# ProPrj_mykeyboard_2025-10-05.net
KiCad netlist of a schematic drawn in EasyEDA Pro
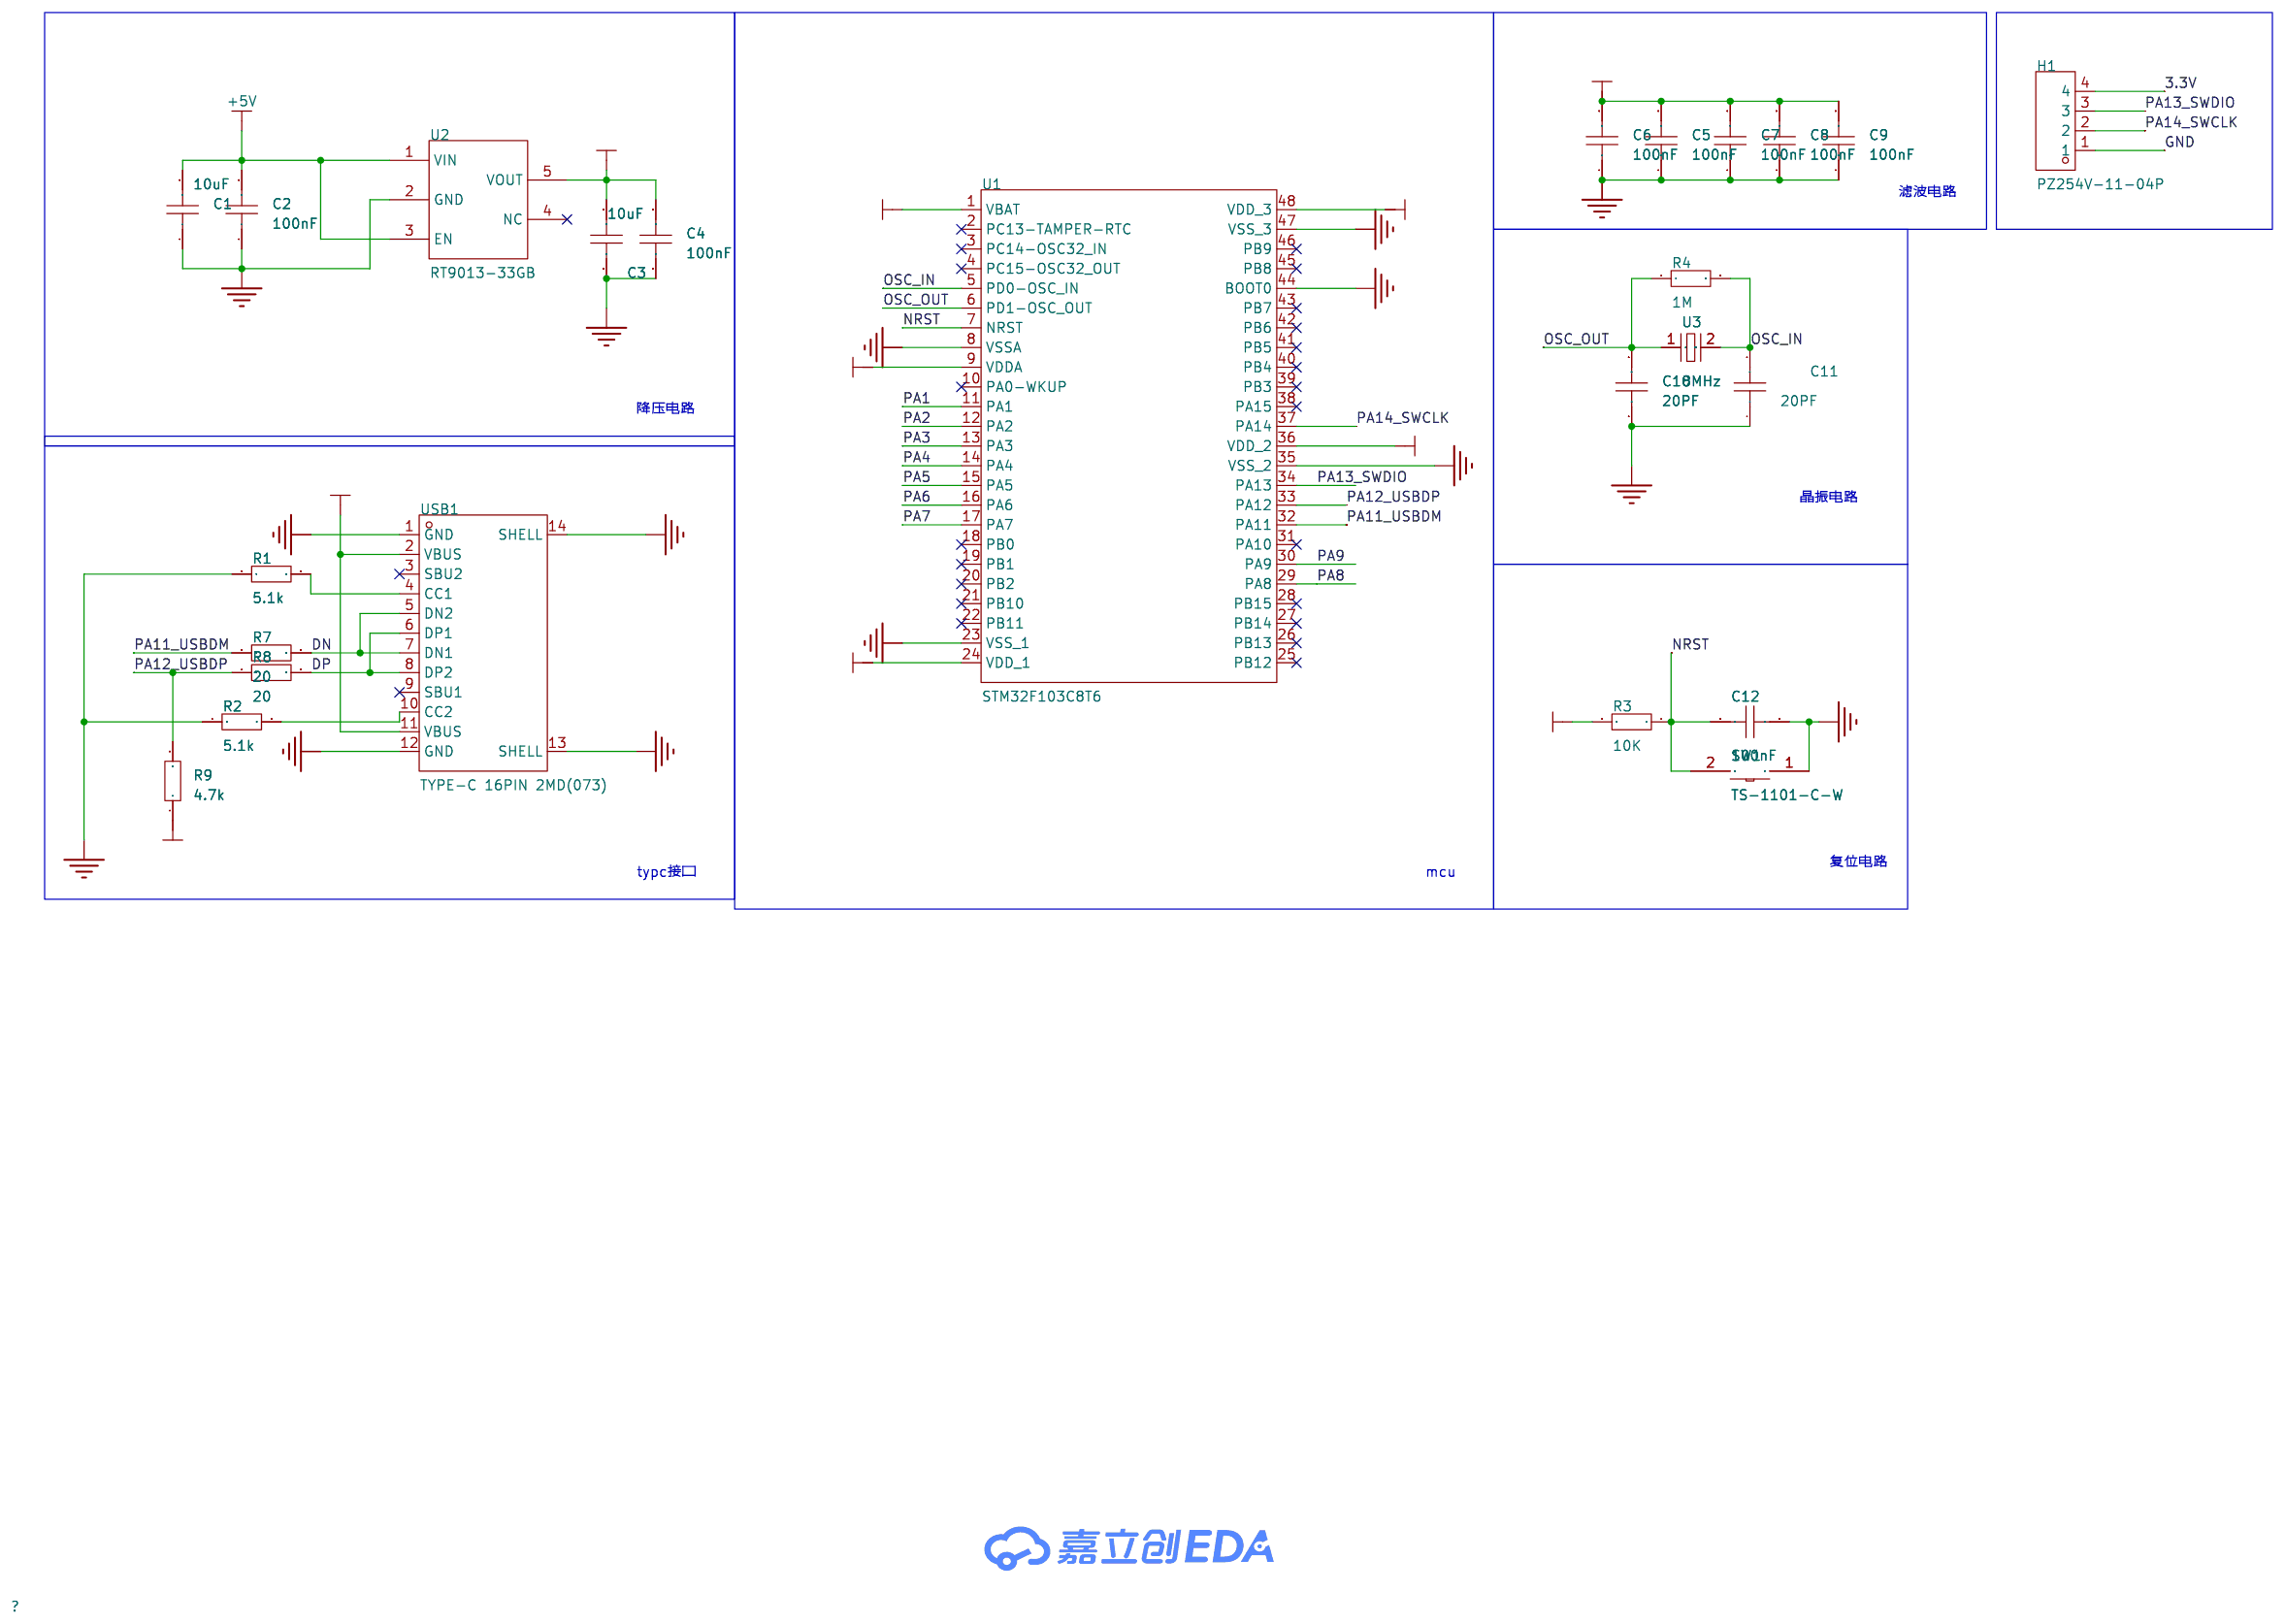
[diagram p0: P1]
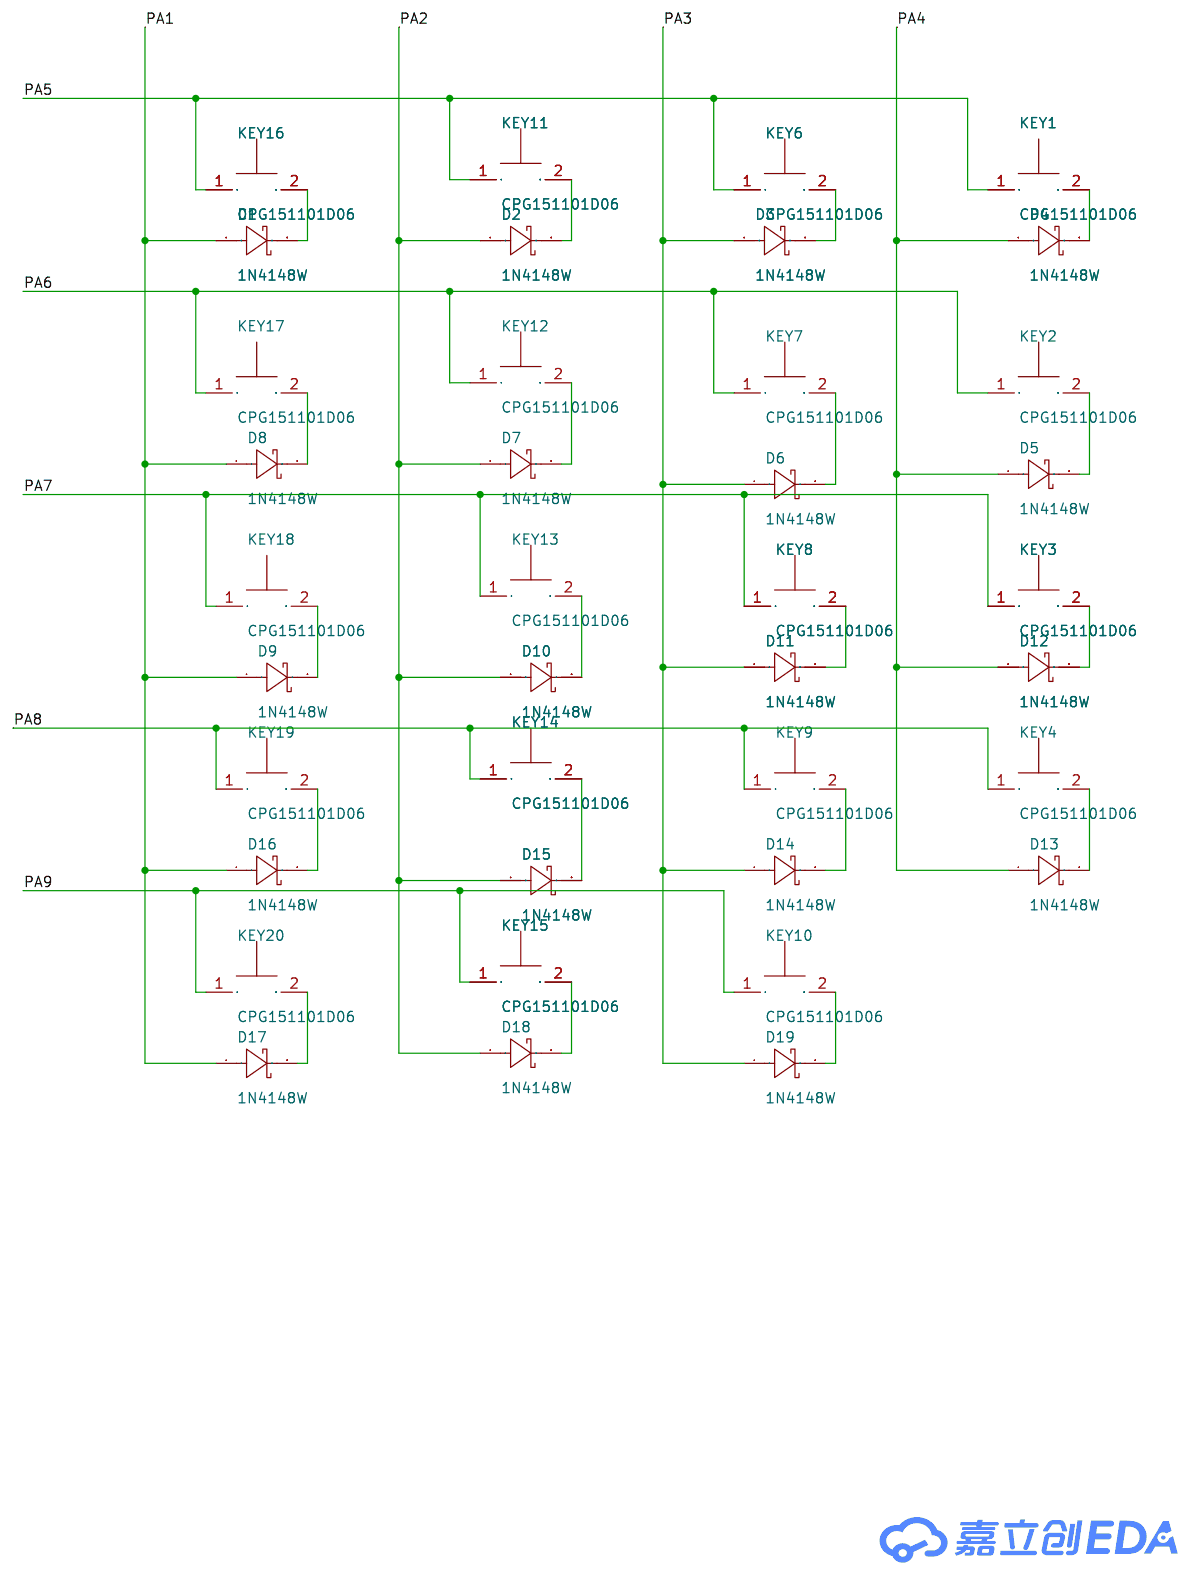
[diagram p1: P2]

(export (version "E")
  (design (tool "Eeschema 10.0.6"))
  (components
    (comp (ref "C1")
      (value "10uF")
      (footprint "easyedapro:C0603")
      (libsource (lib "easyedapro") (part "Capacitance"))
    )
    (comp (ref "C2")
      (value "100nF")
      (footprint "easyedapro:C0603")
      (libsource (lib "easyedapro") (part "Capacitance"))
    )
    (comp (ref "C3")
      (value "10uF")
      (footprint "easyedapro:C0603")
      (libsource (lib "easyedapro") (part "Capacitance"))
    )
    (comp (ref "C4")
      (value "100nF")
      (footprint "easyedapro:C0603")
      (libsource (lib "easyedapro") (part "Capacitance"))
    )
    (comp (ref "C5")
      (value "100nF")
      (footprint "easyedapro:C0603")
      (libsource (lib "easyedapro") (part "Capacitance"))
    )
    (comp (ref "C6")
      (value "100nF")
      (footprint "easyedapro:C0603")
      (libsource (lib "easyedapro") (part "Capacitance"))
    )
    (comp (ref "C7")
      (value "100nF")
      (footprint "easyedapro:C0603")
      (libsource (lib "easyedapro") (part "Capacitance"))
    )
    (comp (ref "C8")
      (value "100nF")
      (footprint "easyedapro:C0603")
      (libsource (lib "easyedapro") (part "Capacitance"))
    )
    (comp (ref "C9")
      (value "100nF")
      (footprint "easyedapro:C0603")
      (libsource (lib "easyedapro") (part "Capacitance"))
    )
    (comp (ref "C10")
      (value "20PF")
      (footprint "easyedapro:C0603")
      (libsource (lib "easyedapro") (part "Capacitance"))
    )
    (comp (ref "C11")
      (value "20PF")
      (footprint "easyedapro:C0603")
      (libsource (lib "easyedapro") (part "Capacitance"))
    )
    (comp (ref "C12")
      (value "100nF")
      (footprint "easyedapro:C0603")
      (libsource (lib "easyedapro") (part "Capacitance"))
    )
    (comp (ref "H1")
      (value "PZ254V-11-04P")
      (footprint "easyedapro:HDR-TH_4P-P2.54-V-M")
      (fields (field (name "Manufacturer") "XFCN(兴飞)"))
      (libsource (lib "easyedapro") (part "PZ254V-11-04P_C2691448"))
    )
    (comp (ref "R1") (value "5.1k") (footprint "easyedapro:R0603") (libsource (lib "easyedapro") (part "电阻")))
    (comp (ref "R2") (value "5.1k") (footprint "easyedapro:R0603") (libsource (lib "easyedapro") (part "电阻")))
    (comp (ref "R3") (value "10K") (footprint "easyedapro:R0603") (libsource (lib "easyedapro") (part "电阻")))
    (comp (ref "R4") (value "1M") (footprint "easyedapro:R0603") (libsource (lib "easyedapro") (part "电阻")))
    (comp (ref "R7") (value "20") (footprint "easyedapro:R0603") (libsource (lib "easyedapro") (part "电阻")))
    (comp (ref "R8") (value "20") (footprint "easyedapro:R0603") (libsource (lib "easyedapro") (part "电阻")))
    (comp (ref "R9") (value "4.7k") (footprint "easyedapro:R0603") (libsource (lib "easyedapro") (part "电阻")))
    (comp (ref "SW1")
      (value "TS-1101-C-W")
      (footprint "easyedapro:SW-SMD_L6.0-W3.3-LS8.0")
      (fields (field (name "Manufacturer") "XKB Connectivity(中国星坤)"))
      (libsource (lib "easyedapro") (part "TS-1101-C-W"))
    )
    (comp (ref "U1")
      (value "STM32F103C8T6")
      (footprint "easyedapro:LQFP-48_L7.0-W7.0-P0.50-LS9.0-BL")
      (description "CPU内核:ARM-M3;CPU最大主频:72MHz;应用领域:-;")
      (fields (field (name "Manufacturer") "ST(意法半导体)"))
      (libsource (lib "easyedapro") (part "STM32F103C8T6"))
    )
    (comp (ref "U2")
      (value "RT9013-33GB")
      (footprint "easyedapro:SOT-23-5_L3.0-W1.7-P0.95-LS2.8-BL")
      (description "输出类型:固定;工作电压:5.5V;输出电压:3.3V;输出电流:500mA;电源纹波抑制比(PSRR):50dB@(10kHz);输出极性:正极;")
      (fields (field (name "Manufacturer") "RICHTEK(立锜)"))
      (libsource (lib "easyedapro") (part "RT9013-33GB"))
    )
    (comp (ref "U3")
      (value "8MHz")
      (footprint "easyedapro:HC-49S_L7.0-W4.0")
      (description "频率:8MHz;常温频差:±20ppm;负载电容:20pF;频率稳定度:±30ppm;")
      (fields (field (name "Manufacturer Part") "8M 20PF 20PPM") (field (name "Manufacturer") "SOSET(索斯特)"))
      (libsource (lib "easyedapro") (part "8M 20PF 20PPM"))
    )
    (comp (ref "USB1")
      (value "TYPE-C 16PIN 2MD(073)")
      (footprint "easyedapro:USB-C-SMD_TYPE-C-6PIN-2MD-073")
      (description "连接器类型:Type-C;协议标准:-;公母:母;安装方式:卧贴;触点数量:16P;端口数量:1;额定电流 - 电源:3A;工作温度:-25°C~+85°C;")
      (fields (field (name "Manufacturer") "SHOU HAN(首韩)"))
      (libsource (lib "easyedapro") (part "TYPE-C 16PIN 2MD(073)"))
    )
    (comp (ref "D1")
      (value "1N4148W")
      (footprint "easyedapro:SOD-123_L2.7-W1.6-LS3.7-FD")
      (description "二极管配置:独立式;正向压降(Vf):1.25V@150mA;直流反向耐压(Vr):100V;整流电流:150mA;反向恢复时间(Trr):4ns;")
      (fields (field (name "Manufacturer") "R+O(宏嘉诚)"))
      (libsource (lib "easyedapro") (part "1N4148W_C7420318"))
    )
    (comp (ref "D2")
      (value "1N4148W")
      (footprint "easyedapro:SOD-123_L2.7-W1.6-LS3.7-FD")
      (description "二极管配置:独立式;正向压降(Vf):1.25V@150mA;直流反向耐压(Vr):100V;整流电流:150mA;反向恢复时间(Trr):4ns;")
      (fields (field (name "Manufacturer") "R+O(宏嘉诚)"))
      (libsource (lib "easyedapro") (part "1N4148W_C7420318"))
    )
    (comp (ref "D3")
      (value "1N4148W")
      (footprint "easyedapro:SOD-123_L2.7-W1.6-LS3.7-FD")
      (description "二极管配置:独立式;正向压降(Vf):1.25V@150mA;直流反向耐压(Vr):100V;整流电流:150mA;反向恢复时间(Trr):4ns;")
      (fields (field (name "Manufacturer") "R+O(宏嘉诚)"))
      (libsource (lib "easyedapro") (part "1N4148W_C7420318"))
    )
    (comp (ref "D4")
      (value "1N4148W")
      (footprint "easyedapro:SOD-123_L2.7-W1.6-LS3.7-FD")
      (description "二极管配置:独立式;正向压降(Vf):1.25V@150mA;直流反向耐压(Vr):100V;整流电流:150mA;反向恢复时间(Trr):4ns;")
      (fields (field (name "Manufacturer") "R+O(宏嘉诚)"))
      (libsource (lib "easyedapro") (part "1N4148W_C7420318"))
    )
    (comp (ref "D5")
      (value "1N4148W")
      (footprint "easyedapro:SOD-123_L2.7-W1.6-LS3.7-FD")
      (description "二极管配置:独立式;正向压降(Vf):1.25V@150mA;直流反向耐压(Vr):100V;整流电流:150mA;反向恢复时间(Trr):4ns;")
      (fields (field (name "Manufacturer") "R+O(宏嘉诚)"))
      (libsource (lib "easyedapro") (part "1N4148W_C7420318"))
    )
    (comp (ref "D6")
      (value "1N4148W")
      (footprint "easyedapro:SOD-123_L2.7-W1.6-LS3.7-FD")
      (description "二极管配置:独立式;正向压降(Vf):1.25V@150mA;直流反向耐压(Vr):100V;整流电流:150mA;反向恢复时间(Trr):4ns;")
      (fields (field (name "Manufacturer") "R+O(宏嘉诚)"))
      (libsource (lib "easyedapro") (part "1N4148W_C7420318"))
    )
    (comp (ref "D7")
      (value "1N4148W")
      (footprint "easyedapro:SOD-123_L2.7-W1.6-LS3.7-FD")
      (description "二极管配置:独立式;正向压降(Vf):1.25V@150mA;直流反向耐压(Vr):100V;整流电流:150mA;反向恢复时间(Trr):4ns;")
      (fields (field (name "Manufacturer") "R+O(宏嘉诚)"))
      (libsource (lib "easyedapro") (part "1N4148W_C7420318"))
    )
    (comp (ref "D8")
      (value "1N4148W")
      (footprint "easyedapro:SOD-123_L2.7-W1.6-LS3.7-FD")
      (description "二极管配置:独立式;正向压降(Vf):1.25V@150mA;直流反向耐压(Vr):100V;整流电流:150mA;反向恢复时间(Trr):4ns;")
      (fields (field (name "Manufacturer") "R+O(宏嘉诚)"))
      (libsource (lib "easyedapro") (part "1N4148W_C7420318"))
    )
    (comp (ref "D9")
      (value "1N4148W")
      (footprint "easyedapro:SOD-123_L2.7-W1.6-LS3.7-FD")
      (description "二极管配置:独立式;正向压降(Vf):1.25V@150mA;直流反向耐压(Vr):100V;整流电流:150mA;反向恢复时间(Trr):4ns;")
      (fields (field (name "Manufacturer") "R+O(宏嘉诚)"))
      (libsource (lib "easyedapro") (part "1N4148W_C7420318"))
    )
    (comp (ref "D10")
      (value "1N4148W")
      (footprint "easyedapro:SOD-123_L2.7-W1.6-LS3.7-FD")
      (description "二极管配置:独立式;正向压降(Vf):1.25V@150mA;直流反向耐压(Vr):100V;整流电流:150mA;反向恢复时间(Trr):4ns;")
      (fields (field (name "Manufacturer") "R+O(宏嘉诚)"))
      (libsource (lib "easyedapro") (part "1N4148W_C7420318"))
    )
    (comp (ref "D11")
      (value "1N4148W")
      (footprint "easyedapro:SOD-123_L2.7-W1.6-LS3.7-FD")
      (description "二极管配置:独立式;正向压降(Vf):1.25V@150mA;直流反向耐压(Vr):100V;整流电流:150mA;反向恢复时间(Trr):4ns;")
      (fields (field (name "Manufacturer") "R+O(宏嘉诚)"))
      (libsource (lib "easyedapro") (part "1N4148W_C7420318"))
    )
    (comp (ref "D12")
      (value "1N4148W")
      (footprint "easyedapro:SOD-123_L2.7-W1.6-LS3.7-FD")
      (description "二极管配置:独立式;正向压降(Vf):1.25V@150mA;直流反向耐压(Vr):100V;整流电流:150mA;反向恢复时间(Trr):4ns;")
      (fields (field (name "Manufacturer") "R+O(宏嘉诚)"))
      (libsource (lib "easyedapro") (part "1N4148W_C7420318"))
    )
    (comp (ref "D13")
      (value "1N4148W")
      (footprint "easyedapro:SOD-123_L2.7-W1.6-LS3.7-FD")
      (description "二极管配置:独立式;正向压降(Vf):1.25V@150mA;直流反向耐压(Vr):100V;整流电流:150mA;反向恢复时间(Trr):4ns;")
      (fields (field (name "Manufacturer") "R+O(宏嘉诚)"))
      (libsource (lib "easyedapro") (part "1N4148W_C7420318"))
    )
    (comp (ref "D14")
      (value "1N4148W")
      (footprint "easyedapro:SOD-123_L2.7-W1.6-LS3.7-FD")
      (description "二极管配置:独立式;正向压降(Vf):1.25V@150mA;直流反向耐压(Vr):100V;整流电流:150mA;反向恢复时间(Trr):4ns;")
      (fields (field (name "Manufacturer") "R+O(宏嘉诚)"))
      (libsource (lib "easyedapro") (part "1N4148W_C7420318"))
    )
    (comp (ref "D15")
      (value "1N4148W")
      (footprint "easyedapro:SOD-123_L2.7-W1.6-LS3.7-FD")
      (description "二极管配置:独立式;正向压降(Vf):1.25V@150mA;直流反向耐压(Vr):100V;整流电流:150mA;反向恢复时间(Trr):4ns;")
      (fields (field (name "Manufacturer") "R+O(宏嘉诚)"))
      (libsource (lib "easyedapro") (part "1N4148W_C7420318"))
    )
    (comp (ref "D16")
      (value "1N4148W")
      (footprint "easyedapro:SOD-123_L2.7-W1.6-LS3.7-FD")
      (description "二极管配置:独立式;正向压降(Vf):1.25V@150mA;直流反向耐压(Vr):100V;整流电流:150mA;反向恢复时间(Trr):4ns;")
      (fields (field (name "Manufacturer") "R+O(宏嘉诚)"))
      (libsource (lib "easyedapro") (part "1N4148W_C7420318"))
    )
    (comp (ref "D17")
      (value "1N4148W")
      (footprint "easyedapro:SOD-123_L2.7-W1.6-LS3.7-FD")
      (description "二极管配置:独立式;正向压降(Vf):1.25V@150mA;直流反向耐压(Vr):100V;整流电流:150mA;反向恢复时间(Trr):4ns;")
      (fields (field (name "Manufacturer") "R+O(宏嘉诚)"))
      (libsource (lib "easyedapro") (part "1N4148W_C7420318"))
    )
    (comp (ref "D18")
      (value "1N4148W")
      (footprint "easyedapro:SOD-123_L2.7-W1.6-LS3.7-FD")
      (description "二极管配置:独立式;正向压降(Vf):1.25V@150mA;直流反向耐压(Vr):100V;整流电流:150mA;反向恢复时间(Trr):4ns;")
      (fields (field (name "Manufacturer") "R+O(宏嘉诚)"))
      (libsource (lib "easyedapro") (part "1N4148W_C7420318"))
    )
    (comp (ref "D19")
      (value "1N4148W")
      (footprint "easyedapro:SOD-123_L2.7-W1.6-LS3.7-FD")
      (description "二极管配置:独立式;正向压降(Vf):1.25V@150mA;直流反向耐压(Vr):100V;整流电流:150mA;反向恢复时间(Trr):4ns;")
      (fields (field (name "Manufacturer") "R+O(宏嘉诚)"))
      (libsource (lib "easyedapro") (part "1N4148W_C7420318"))
    )
    (comp (ref "KEY1")
      (value "CPG151101D06")
      (footprint "easyedapro:KEY-TH_CPG151101D06")
      (description "机械键盘开关MX茶轴 段落手感")
      (fields (field (name "Manufacturer") "HanElectricity(瀚源)"))
      (libsource (lib "easyedapro") (part "CPG151101D06"))
    )
    (comp (ref "KEY2")
      (value "CPG151101D06")
      (footprint "easyedapro:KEY-TH_CPG151101D06")
      (description "机械键盘开关MX茶轴 段落手感")
      (fields (field (name "Manufacturer") "HanElectricity(瀚源)"))
      (libsource (lib "easyedapro") (part "CPG151101D06"))
    )
    (comp (ref "KEY3")
      (value "CPG151101D06")
      (footprint "easyedapro:KEY-TH_CPG151101D06")
      (description "机械键盘开关MX茶轴 段落手感")
      (fields (field (name "Manufacturer") "HanElectricity(瀚源)"))
      (libsource (lib "easyedapro") (part "CPG151101D06"))
    )
    (comp (ref "KEY4")
      (value "CPG151101D06")
      (footprint "easyedapro:KEY-TH_CPG151101D06")
      (description "机械键盘开关MX茶轴 段落手感")
      (fields (field (name "Manufacturer") "HanElectricity(瀚源)"))
      (libsource (lib "easyedapro") (part "CPG151101D06"))
    )
    (comp (ref "KEY6")
      (value "CPG151101D06")
      (footprint "easyedapro:KEY-TH_CPG151101D06")
      (description "机械键盘开关MX茶轴 段落手感")
      (fields (field (name "Manufacturer") "HanElectricity(瀚源)"))
      (libsource (lib "easyedapro") (part "CPG151101D06"))
    )
    (comp (ref "KEY7")
      (value "CPG151101D06")
      (footprint "easyedapro:KEY-TH_CPG151101D06")
      (description "机械键盘开关MX茶轴 段落手感")
      (fields (field (name "Manufacturer") "HanElectricity(瀚源)"))
      (libsource (lib "easyedapro") (part "CPG151101D06"))
    )
    (comp (ref "KEY8")
      (value "CPG151101D06")
      (footprint "easyedapro:KEY-TH_CPG151101D06")
      (description "机械键盘开关MX茶轴 段落手感")
      (fields (field (name "Manufacturer") "HanElectricity(瀚源)"))
      (libsource (lib "easyedapro") (part "CPG151101D06"))
    )
    (comp (ref "KEY9")
      (value "CPG151101D06")
      (footprint "easyedapro:KEY-TH_CPG151101D06")
      (description "机械键盘开关MX茶轴 段落手感")
      (fields (field (name "Manufacturer") "HanElectricity(瀚源)"))
      (libsource (lib "easyedapro") (part "CPG151101D06"))
    )
    (comp (ref "KEY10")
      (value "CPG151101D06")
      (footprint "easyedapro:KEY-TH_CPG151101D06")
      (description "机械键盘开关MX茶轴 段落手感")
      (fields (field (name "Manufacturer") "HanElectricity(瀚源)"))
      (libsource (lib "easyedapro") (part "CPG151101D06"))
    )
    (comp (ref "KEY11")
      (value "CPG151101D06")
      (footprint "easyedapro:KEY-TH_CPG151101D06")
      (description "机械键盘开关MX茶轴 段落手感")
      (fields (field (name "Manufacturer") "HanElectricity(瀚源)"))
      (libsource (lib "easyedapro") (part "CPG151101D06"))
    )
    (comp (ref "KEY12")
      (value "CPG151101D06")
      (footprint "easyedapro:KEY-TH_CPG151101D06")
      (description "机械键盘开关MX茶轴 段落手感")
      (fields (field (name "Manufacturer") "HanElectricity(瀚源)"))
      (libsource (lib "easyedapro") (part "CPG151101D06"))
    )
    (comp (ref "KEY13")
      (value "CPG151101D06")
      (footprint "easyedapro:KEY-TH_CPG151101D06")
      (description "机械键盘开关MX茶轴 段落手感")
      (fields (field (name "Manufacturer") "HanElectricity(瀚源)"))
      (libsource (lib "easyedapro") (part "CPG151101D06"))
    )
    (comp (ref "KEY14")
      (value "CPG151101D06")
      (footprint "easyedapro:KEY-TH_CPG151101D06")
      (description "机械键盘开关MX茶轴 段落手感")
      (fields (field (name "Manufacturer") "HanElectricity(瀚源)"))
      (libsource (lib "easyedapro") (part "CPG151101D06"))
    )
    (comp (ref "KEY15")
      (value "CPG151101D06")
      (footprint "easyedapro:KEY-TH_CPG151101D06")
      (description "机械键盘开关MX茶轴 段落手感")
      (fields (field (name "Manufacturer") "HanElectricity(瀚源)"))
      (libsource (lib "easyedapro") (part "CPG151101D06"))
    )
    (comp (ref "KEY16")
      (value "CPG151101D06")
      (footprint "easyedapro:KEY-TH_CPG151101D06")
      (description "机械键盘开关MX茶轴 段落手感")
      (fields (field (name "Manufacturer") "HanElectricity(瀚源)"))
      (libsource (lib "easyedapro") (part "CPG151101D06"))
    )
    (comp (ref "KEY17")
      (value "CPG151101D06")
      (footprint "easyedapro:KEY-TH_CPG151101D06")
      (description "机械键盘开关MX茶轴 段落手感")
      (fields (field (name "Manufacturer") "HanElectricity(瀚源)"))
      (libsource (lib "easyedapro") (part "CPG151101D06"))
    )
    (comp (ref "KEY18")
      (value "CPG151101D06")
      (footprint "easyedapro:KEY-TH_CPG151101D06")
      (description "机械键盘开关MX茶轴 段落手感")
      (fields (field (name "Manufacturer") "HanElectricity(瀚源)"))
      (libsource (lib "easyedapro") (part "CPG151101D06"))
    )
    (comp (ref "KEY19")
      (value "CPG151101D06")
      (footprint "easyedapro:KEY-TH_CPG151101D06")
      (description "机械键盘开关MX茶轴 段落手感")
      (fields (field (name "Manufacturer") "HanElectricity(瀚源)"))
      (libsource (lib "easyedapro") (part "CPG151101D06"))
    )
    (comp (ref "KEY20")
      (value "CPG151101D06")
      (footprint "easyedapro:KEY-TH_CPG151101D06")
      (description "机械键盘开关MX茶轴 段落手感")
      (fields (field (name "Manufacturer") "HanElectricity(瀚源)"))
      (libsource (lib "easyedapro") (part "CPG151101D06"))
    )
  )
  (nets
    (net (code "1") (name "+5V") (class "Default")
      (node (ref "C1") (pin "2") (pinfunction "2_2") (pintype "input"))
      (node (ref "C2") (pin "2") (pinfunction "2_2") (pintype "input"))
      (node (ref "U2") (pin "1") (pinfunction "VIN_1") (pintype "unspecified"))
      (node (ref "U2") (pin "3") (pinfunction "EN_3") (pintype "unspecified"))
      (node (ref "USB1") (pin "11") (pinfunction "VBUS_11") (pintype "unspecified"))
      (node (ref "USB1") (pin "2") (pinfunction "VBUS_2") (pintype "unspecified"))
    )
    (net (code "2") (name "3.3V") (class "Default")
      (node (ref "C3") (pin "2") (pinfunction "2_2") (pintype "input"))
      (node (ref "C4") (pin "2") (pinfunction "2_2") (pintype "input"))
      (node (ref "C5") (pin "2") (pinfunction "2_2") (pintype "input"))
      (node (ref "C6") (pin "2") (pinfunction "2_2") (pintype "input"))
      (node (ref "C7") (pin "2") (pinfunction "2_2") (pintype "input"))
      (node (ref "C8") (pin "2") (pinfunction "2_2") (pintype "input"))
      (node (ref "C9") (pin "2") (pinfunction "2_2") (pintype "input"))
      (node (ref "H1") (pin "4") (pinfunction "4_4") (pintype "unspecified"))
      (node (ref "R3") (pin "2") (pinfunction "2_2") (pintype "input"))
      (node (ref "R9") (pin "1") (pinfunction "1_1") (pintype "input"))
      (node (ref "U1") (pin "1") (pinfunction "VBAT_1") (pintype "unspecified"))
      (node (ref "U1") (pin "24") (pinfunction "VDD_1_24") (pintype "unspecified"))
      (node (ref "U1") (pin "36") (pinfunction "VDD_2_36") (pintype "unspecified"))
      (node (ref "U1") (pin "48") (pinfunction "VDD_3_48") (pintype "unspecified"))
      (node (ref "U1") (pin "9") (pinfunction "VDDA_9") (pintype "unspecified"))
      (node (ref "U2") (pin "5") (pinfunction "VOUT_5") (pintype "unspecified"))
    )
    (net (code "3") (name "DN") (class "Default")
      (node (ref "R7") (pin "2") (pinfunction "2_2") (pintype "input"))
      (node (ref "USB1") (pin "5") (pinfunction "DN2_5") (pintype "unspecified"))
      (node (ref "USB1") (pin "7") (pinfunction "DN1_7") (pintype "unspecified"))
    )
    (net (code "4") (name "DP") (class "Default")
      (node (ref "R8") (pin "2") (pinfunction "2_2") (pintype "input"))
      (node (ref "USB1") (pin "6") (pinfunction "DP1_6") (pintype "unspecified"))
      (node (ref "USB1") (pin "8") (pinfunction "DP2_8") (pintype "unspecified"))
    )
    (net (code "5") (name "GND") (class "Default")
      (node (ref "C1") (pin "1") (pinfunction "1_1") (pintype "input"))
      (node (ref "C10") (pin "1") (pinfunction "1_1") (pintype "input"))
      (node (ref "C11") (pin "1") (pinfunction "1_1") (pintype "input"))
      (node (ref "C12") (pin "1") (pinfunction "1_1") (pintype "input"))
      (node (ref "C2") (pin "1") (pinfunction "1_1") (pintype "input"))
      (node (ref "C3") (pin "1") (pinfunction "1_1") (pintype "input"))
      (node (ref "C4") (pin "1") (pinfunction "1_1") (pintype "input"))
      (node (ref "C5") (pin "1") (pinfunction "1_1") (pintype "input"))
      (node (ref "C6") (pin "1") (pinfunction "1_1") (pintype "input"))
      (node (ref "C7") (pin "1") (pinfunction "1_1") (pintype "input"))
      (node (ref "C8") (pin "1") (pinfunction "1_1") (pintype "input"))
      (node (ref "C9") (pin "1") (pinfunction "1_1") (pintype "input"))
      (node (ref "H1") (pin "1") (pinfunction "1_1") (pintype "unspecified"))
      (node (ref "R1") (pin "1") (pinfunction "1_1") (pintype "input"))
      (node (ref "R2") (pin "1") (pinfunction "1_1") (pintype "input"))
      (node (ref "SW1") (pin "1") (pinfunction "1_1") (pintype "unspecified"))
      (node (ref "U1") (pin "23") (pinfunction "VSS_1_23") (pintype "unspecified"))
      (node (ref "U1") (pin "35") (pinfunction "VSS_2_35") (pintype "unspecified"))
      (node (ref "U1") (pin "44") (pinfunction "BOOT0_44") (pintype "unspecified"))
      (node (ref "U1") (pin "47") (pinfunction "VSS_3_47") (pintype "unspecified"))
      (node (ref "U1") (pin "8") (pinfunction "VSSA_8") (pintype "unspecified"))
      (node (ref "U2") (pin "2") (pinfunction "GND_2") (pintype "unspecified"))
      (node (ref "USB1") (pin "1") (pinfunction "GND_1") (pintype "unspecified"))
      (node (ref "USB1") (pin "12") (pinfunction "GND_12") (pintype "unspecified"))
      (node (ref "USB1") (pin "13") (pinfunction "SHELL_13") (pintype "unspecified"))
      (node (ref "USB1") (pin "14") (pinfunction "SHELL_14") (pintype "unspecified"))
    )
    (net (code "6") (name "NRST") (class "Default")
      (node (ref "C12") (pin "2") (pinfunction "2_2") (pintype "input"))
      (node (ref "R3") (pin "1") (pinfunction "1_1") (pintype "input"))
      (node (ref "SW1") (pin "2") (pinfunction "2_2") (pintype "unspecified"))
      (node (ref "U1") (pin "7") (pinfunction "NRST_7") (pintype "unspecified"))
    )
    (net (code "7") (name "Net-(D1-K)") (class "Default")
      (node (ref "D1") (pin "2") (pinfunction "K_2") (pintype "unspecified"))
      (node (ref "KEY16") (pin "2") (pinfunction "2_2") (pintype "unspecified"))
    )
    (net (code "8") (name "Net-(D2-K)") (class "Default")
      (node (ref "D2") (pin "2") (pinfunction "K_2") (pintype "unspecified"))
      (node (ref "KEY11") (pin "2") (pinfunction "2_2") (pintype "unspecified"))
    )
    (net (code "9") (name "Net-(D3-K)") (class "Default")
      (node (ref "D3") (pin "2") (pinfunction "K_2") (pintype "unspecified"))
      (node (ref "KEY6") (pin "2") (pinfunction "2_2") (pintype "unspecified"))
    )
    (net (code "10") (name "Net-(D4-K)") (class "Default")
      (node (ref "D4") (pin "2") (pinfunction "K_2") (pintype "unspecified"))
      (node (ref "KEY1") (pin "2") (pinfunction "2_2") (pintype "unspecified"))
    )
    (net (code "11") (name "Net-(D5-K)") (class "Default")
      (node (ref "D5") (pin "2") (pinfunction "K_2") (pintype "unspecified"))
      (node (ref "KEY2") (pin "2") (pinfunction "2_2") (pintype "unspecified"))
    )
    (net (code "12") (name "Net-(D6-K)") (class "Default")
      (node (ref "D6") (pin "2") (pinfunction "K_2") (pintype "unspecified"))
      (node (ref "KEY7") (pin "2") (pinfunction "2_2") (pintype "unspecified"))
    )
    (net (code "13") (name "Net-(D7-K)") (class "Default")
      (node (ref "D7") (pin "2") (pinfunction "K_2") (pintype "unspecified"))
      (node (ref "KEY12") (pin "2") (pinfunction "2_2") (pintype "unspecified"))
    )
    (net (code "14") (name "Net-(D8-K)") (class "Default")
      (node (ref "D8") (pin "2") (pinfunction "K_2") (pintype "unspecified"))
      (node (ref "KEY17") (pin "2") (pinfunction "2_2") (pintype "unspecified"))
    )
    (net (code "15") (name "Net-(D9-K)") (class "Default")
      (node (ref "D9") (pin "2") (pinfunction "K_2") (pintype "unspecified"))
      (node (ref "KEY18") (pin "2") (pinfunction "2_2") (pintype "unspecified"))
    )
    (net (code "16") (name "Net-(D10-K)") (class "Default")
      (node (ref "D10") (pin "2") (pinfunction "K_2") (pintype "unspecified"))
      (node (ref "KEY13") (pin "2") (pinfunction "2_2") (pintype "unspecified"))
    )
    (net (code "17") (name "Net-(D11-K)") (class "Default")
      (node (ref "D11") (pin "2") (pinfunction "K_2") (pintype "unspecified"))
      (node (ref "KEY8") (pin "2") (pinfunction "2_2") (pintype "unspecified"))
    )
    (net (code "18") (name "Net-(D12-K)") (class "Default")
      (node (ref "D12") (pin "2") (pinfunction "K_2") (pintype "unspecified"))
      (node (ref "KEY3") (pin "2") (pinfunction "2_2") (pintype "unspecified"))
    )
    (net (code "19") (name "Net-(D13-K)") (class "Default")
      (node (ref "D13") (pin "2") (pinfunction "K_2") (pintype "unspecified"))
      (node (ref "KEY4") (pin "2") (pinfunction "2_2") (pintype "unspecified"))
    )
    (net (code "20") (name "Net-(D14-K)") (class "Default")
      (node (ref "D14") (pin "2") (pinfunction "K_2") (pintype "unspecified"))
      (node (ref "KEY9") (pin "2") (pinfunction "2_2") (pintype "unspecified"))
    )
    (net (code "21") (name "Net-(D15-K)") (class "Default")
      (node (ref "D15") (pin "2") (pinfunction "K_2") (pintype "unspecified"))
      (node (ref "KEY14") (pin "2") (pinfunction "2_2") (pintype "unspecified"))
    )
    (net (code "22") (name "Net-(D16-K)") (class "Default")
      (node (ref "D16") (pin "2") (pinfunction "K_2") (pintype "unspecified"))
      (node (ref "KEY19") (pin "2") (pinfunction "2_2") (pintype "unspecified"))
    )
    (net (code "23") (name "Net-(D17-K)") (class "Default")
      (node (ref "D17") (pin "2") (pinfunction "K_2") (pintype "unspecified"))
      (node (ref "KEY20") (pin "2") (pinfunction "2_2") (pintype "unspecified"))
    )
    (net (code "24") (name "Net-(D18-K)") (class "Default")
      (node (ref "D18") (pin "2") (pinfunction "K_2") (pintype "unspecified"))
      (node (ref "KEY15") (pin "2") (pinfunction "2_2") (pintype "unspecified"))
    )
    (net (code "25") (name "Net-(D19-K)") (class "Default")
      (node (ref "D19") (pin "2") (pinfunction "K_2") (pintype "unspecified"))
      (node (ref "KEY10") (pin "2") (pinfunction "2_2") (pintype "unspecified"))
    )
    (net (code "26") (name "Net-(USB1-CC1)") (class "Default")
      (node (ref "R1") (pin "2") (pinfunction "2_2") (pintype "input"))
      (node (ref "USB1") (pin "4") (pinfunction "CC1_4") (pintype "unspecified"))
    )
    (net (code "27") (name "Net-(USB1-CC2)") (class "Default")
      (node (ref "R2") (pin "2") (pinfunction "2_2") (pintype "input"))
      (node (ref "USB1") (pin "10") (pinfunction "CC2_10") (pintype "unspecified"))
    )
    (net (code "28") (name "OSC_IN") (class "Default")
      (node (ref "C11") (pin "2") (pinfunction "2_2") (pintype "input"))
      (node (ref "R4") (pin "2") (pinfunction "2_2") (pintype "input"))
      (node (ref "U1") (pin "5") (pinfunction "PD0-OSC_IN_5") (pintype "unspecified"))
      (node (ref "U3") (pin "2") (pinfunction "GND_2") (pintype "input"))
    )
    (net (code "29") (name "OSC_OUT") (class "Default")
      (node (ref "C10") (pin "2") (pinfunction "2_2") (pintype "input"))
      (node (ref "R4") (pin "1") (pinfunction "1_1") (pintype "input"))
      (node (ref "U1") (pin "6") (pinfunction "PD1-OSC_OUT_6") (pintype "unspecified"))
      (node (ref "U3") (pin "1") (pinfunction "1_1") (pintype "input"))
    )
    (net (code "30") (name "PA1") (class "Default")
      (node (ref "D1") (pin "1") (pinfunction "A_1") (pintype "unspecified"))
      (node (ref "D16") (pin "1") (pinfunction "A_1") (pintype "unspecified"))
      (node (ref "D17") (pin "1") (pinfunction "A_1") (pintype "unspecified"))
      (node (ref "D8") (pin "1") (pinfunction "A_1") (pintype "unspecified"))
      (node (ref "D9") (pin "1") (pinfunction "A_1") (pintype "unspecified"))
      (node (ref "U1") (pin "11") (pinfunction "PA1_11") (pintype "unspecified"))
    )
    (net (code "31") (name "PA2") (class "Default")
      (node (ref "D10") (pin "1") (pinfunction "A_1") (pintype "unspecified"))
      (node (ref "D15") (pin "1") (pinfunction "A_1") (pintype "unspecified"))
      (node (ref "D18") (pin "1") (pinfunction "A_1") (pintype "unspecified"))
      (node (ref "D2") (pin "1") (pinfunction "A_1") (pintype "unspecified"))
      (node (ref "D7") (pin "1") (pinfunction "A_1") (pintype "unspecified"))
      (node (ref "U1") (pin "12") (pinfunction "PA2_12") (pintype "unspecified"))
    )
    (net (code "32") (name "PA3") (class "Default")
      (node (ref "D11") (pin "1") (pinfunction "A_1") (pintype "unspecified"))
      (node (ref "D14") (pin "1") (pinfunction "A_1") (pintype "unspecified"))
      (node (ref "D19") (pin "1") (pinfunction "A_1") (pintype "unspecified"))
      (node (ref "D3") (pin "1") (pinfunction "A_1") (pintype "unspecified"))
      (node (ref "D6") (pin "1") (pinfunction "A_1") (pintype "unspecified"))
      (node (ref "U1") (pin "13") (pinfunction "PA3_13") (pintype "unspecified"))
    )
    (net (code "33") (name "PA4") (class "Default")
      (node (ref "D12") (pin "1") (pinfunction "A_1") (pintype "unspecified"))
      (node (ref "D13") (pin "1") (pinfunction "A_1") (pintype "unspecified"))
      (node (ref "D4") (pin "1") (pinfunction "A_1") (pintype "unspecified"))
      (node (ref "D5") (pin "1") (pinfunction "A_1") (pintype "unspecified"))
      (node (ref "U1") (pin "14") (pinfunction "PA4_14") (pintype "unspecified"))
    )
    (net (code "34") (name "PA5") (class "Default")
      (node (ref "KEY1") (pin "1") (pinfunction "1_1") (pintype "unspecified"))
      (node (ref "KEY11") (pin "1") (pinfunction "1_1") (pintype "unspecified"))
      (node (ref "KEY16") (pin "1") (pinfunction "1_1") (pintype "unspecified"))
      (node (ref "KEY6") (pin "1") (pinfunction "1_1") (pintype "unspecified"))
      (node (ref "U1") (pin "15") (pinfunction "PA5_15") (pintype "unspecified"))
    )
    (net (code "35") (name "PA6") (class "Default")
      (node (ref "KEY12") (pin "1") (pinfunction "1_1") (pintype "unspecified"))
      (node (ref "KEY17") (pin "1") (pinfunction "1_1") (pintype "unspecified"))
      (node (ref "KEY2") (pin "1") (pinfunction "1_1") (pintype "unspecified"))
      (node (ref "KEY7") (pin "1") (pinfunction "1_1") (pintype "unspecified"))
      (node (ref "U1") (pin "16") (pinfunction "PA6_16") (pintype "unspecified"))
    )
    (net (code "36") (name "PA7") (class "Default")
      (node (ref "KEY13") (pin "1") (pinfunction "1_1") (pintype "unspecified"))
      (node (ref "KEY18") (pin "1") (pinfunction "1_1") (pintype "unspecified"))
      (node (ref "KEY3") (pin "1") (pinfunction "1_1") (pintype "unspecified"))
      (node (ref "KEY8") (pin "1") (pinfunction "1_1") (pintype "unspecified"))
      (node (ref "U1") (pin "17") (pinfunction "PA7_17") (pintype "unspecified"))
    )
    (net (code "37") (name "PA8") (class "Default")
      (node (ref "KEY14") (pin "1") (pinfunction "1_1") (pintype "unspecified"))
      (node (ref "KEY19") (pin "1") (pinfunction "1_1") (pintype "unspecified"))
      (node (ref "KEY4") (pin "1") (pinfunction "1_1") (pintype "unspecified"))
      (node (ref "KEY9") (pin "1") (pinfunction "1_1") (pintype "unspecified"))
      (node (ref "U1") (pin "29") (pinfunction "PA8_29") (pintype "unspecified"))
    )
    (net (code "38") (name "PA9") (class "Default")
      (node (ref "KEY10") (pin "1") (pinfunction "1_1") (pintype "unspecified"))
      (node (ref "KEY15") (pin "1") (pinfunction "1_1") (pintype "unspecified"))
      (node (ref "KEY20") (pin "1") (pinfunction "1_1") (pintype "unspecified"))
      (node (ref "U1") (pin "30") (pinfunction "PA9_30") (pintype "unspecified"))
    )
    (net (code "39") (name "PA11_USBDM") (class "Default")
      (node (ref "R7") (pin "1") (pinfunction "1_1") (pintype "input"))
      (node (ref "U1") (pin "32") (pinfunction "PA11_32") (pintype "unspecified"))
    )
    (net (code "40") (name "PA12_USBDP") (class "Default")
      (node (ref "R8") (pin "1") (pinfunction "1_1") (pintype "input"))
      (node (ref "R9") (pin "2") (pinfunction "2_2") (pintype "input"))
      (node (ref "U1") (pin "33") (pinfunction "PA12_33") (pintype "unspecified"))
    )
    (net (code "41") (name "PA13_SWDIO") (class "Default")
      (node (ref "H1") (pin "3") (pinfunction "3_3") (pintype "unspecified"))
      (node (ref "U1") (pin "34") (pinfunction "PA13_34") (pintype "unspecified"))
    )
    (net (code "42") (name "PA14_SWCLK") (class "Default")
      (node (ref "H1") (pin "2") (pinfunction "2_2") (pintype "unspecified"))
      (node (ref "U1") (pin "37") (pinfunction "PA14_37") (pintype "unspecified"))
    )
    (net (code "43") (name "unconnected-(U1-PA0-WKUP-Pad10)") (class "Default")
      (node (ref "U1") (pin "10") (pinfunction "PA0-WKUP_10") (pintype "unspecified+no_connect"))
    )
    (net (code "44") (name "unconnected-(U1-PA10-Pad31)") (class "Default")
      (node (ref "U1") (pin "31") (pinfunction "PA10_31") (pintype "unspecified+no_connect"))
    )
    (net (code "45") (name "unconnected-(U1-PA15-Pad38)") (class "Default")
      (node (ref "U1") (pin "38") (pinfunction "PA15_38") (pintype "unspecified+no_connect"))
    )
    (net (code "46") (name "unconnected-(U1-PB0-Pad18)") (class "Default")
      (node (ref "U1") (pin "18") (pinfunction "PB0_18") (pintype "unspecified+no_connect"))
    )
    (net (code "47") (name "unconnected-(U1-PB1-Pad19)") (class "Default")
      (node (ref "U1") (pin "19") (pinfunction "PB1_19") (pintype "unspecified+no_connect"))
    )
    (net (code "48") (name "unconnected-(U1-PB2-Pad20)") (class "Default")
      (node (ref "U1") (pin "20") (pinfunction "PB2_20") (pintype "unspecified+no_connect"))
    )
    (net (code "49") (name "unconnected-(U1-PB3-Pad39)") (class "Default")
      (node (ref "U1") (pin "39") (pinfunction "PB3_39") (pintype "unspecified+no_connect"))
    )
    (net (code "50") (name "unconnected-(U1-PB4-Pad40)") (class "Default")
      (node (ref "U1") (pin "40") (pinfunction "PB4_40") (pintype "unspecified+no_connect"))
    )
    (net (code "51") (name "unconnected-(U1-PB5-Pad41)") (class "Default")
      (node (ref "U1") (pin "41") (pinfunction "PB5_41") (pintype "unspecified+no_connect"))
    )
    (net (code "52") (name "unconnected-(U1-PB6-Pad42)") (class "Default")
      (node (ref "U1") (pin "42") (pinfunction "PB6_42") (pintype "unspecified+no_connect"))
    )
    (net (code "53") (name "unconnected-(U1-PB7-Pad43)") (class "Default")
      (node (ref "U1") (pin "43") (pinfunction "PB7_43") (pintype "unspecified+no_connect"))
    )
    (net (code "54") (name "unconnected-(U1-PB8-Pad45)") (class "Default")
      (node (ref "U1") (pin "45") (pinfunction "PB8_45") (pintype "unspecified+no_connect"))
    )
    (net (code "55") (name "unconnected-(U1-PB9-Pad46)") (class "Default")
      (node (ref "U1") (pin "46") (pinfunction "PB9_46") (pintype "unspecified+no_connect"))
    )
    (net (code "56") (name "unconnected-(U1-PB10-Pad21)") (class "Default")
      (node (ref "U1") (pin "21") (pinfunction "PB10_21") (pintype "unspecified+no_connect"))
    )
    (net (code "57") (name "unconnected-(U1-PB11-Pad22)") (class "Default")
      (node (ref "U1") (pin "22") (pinfunction "PB11_22") (pintype "unspecified+no_connect"))
    )
    (net (code "58") (name "unconnected-(U1-PB12-Pad25)") (class "Default")
      (node (ref "U1") (pin "25") (pinfunction "PB12_25") (pintype "unspecified+no_connect"))
    )
    (net (code "59") (name "unconnected-(U1-PB13-Pad26)") (class "Default")
      (node (ref "U1") (pin "26") (pinfunction "PB13_26") (pintype "unspecified+no_connect"))
    )
    (net (code "60") (name "unconnected-(U1-PB14-Pad27)") (class "Default")
      (node (ref "U1") (pin "27") (pinfunction "PB14_27") (pintype "unspecified+no_connect"))
    )
    (net (code "61") (name "unconnected-(U1-PB15-Pad28)") (class "Default")
      (node (ref "U1") (pin "28") (pinfunction "PB15_28") (pintype "unspecified+no_connect"))
    )
    (net (code "62") (name "unconnected-(U1-PC13-TAMPER-RTC-Pad2)") (class "Default")
      (node (ref "U1") (pin "2") (pinfunction "PC13-TAMPER-RTC_2") (pintype "unspecified+no_connect"))
    )
    (net (code "63") (name "unconnected-(U1-PC14-OSC32_IN-Pad3)") (class "Default")
      (node (ref "U1") (pin "3") (pinfunction "PC14-OSC32_IN_3") (pintype "unspecified+no_connect"))
    )
    (net (code "64") (name "unconnected-(U1-PC15-OSC32_OUT-Pad4)") (class "Default")
      (node (ref "U1") (pin "4") (pinfunction "PC15-OSC32_OUT_4") (pintype "unspecified+no_connect"))
    )
    (net (code "65") (name "unconnected-(U2-NC-Pad4)") (class "Default")
      (node (ref "U2") (pin "4") (pinfunction "NC_4") (pintype "unspecified+no_connect"))
    )
    (net (code "66") (name "unconnected-(USB1-SBU1-Pad9)") (class "Default")
      (node (ref "USB1") (pin "9") (pinfunction "SBU1_9") (pintype "unspecified+no_connect"))
    )
    (net (code "67") (name "unconnected-(USB1-SBU2-Pad3)") (class "Default")
      (node (ref "USB1") (pin "3") (pinfunction "SBU2_3") (pintype "unspecified+no_connect"))
    )
  )
)
